# ComponentTester.net
KiCad netlist of a schematic drawn in EAGLE
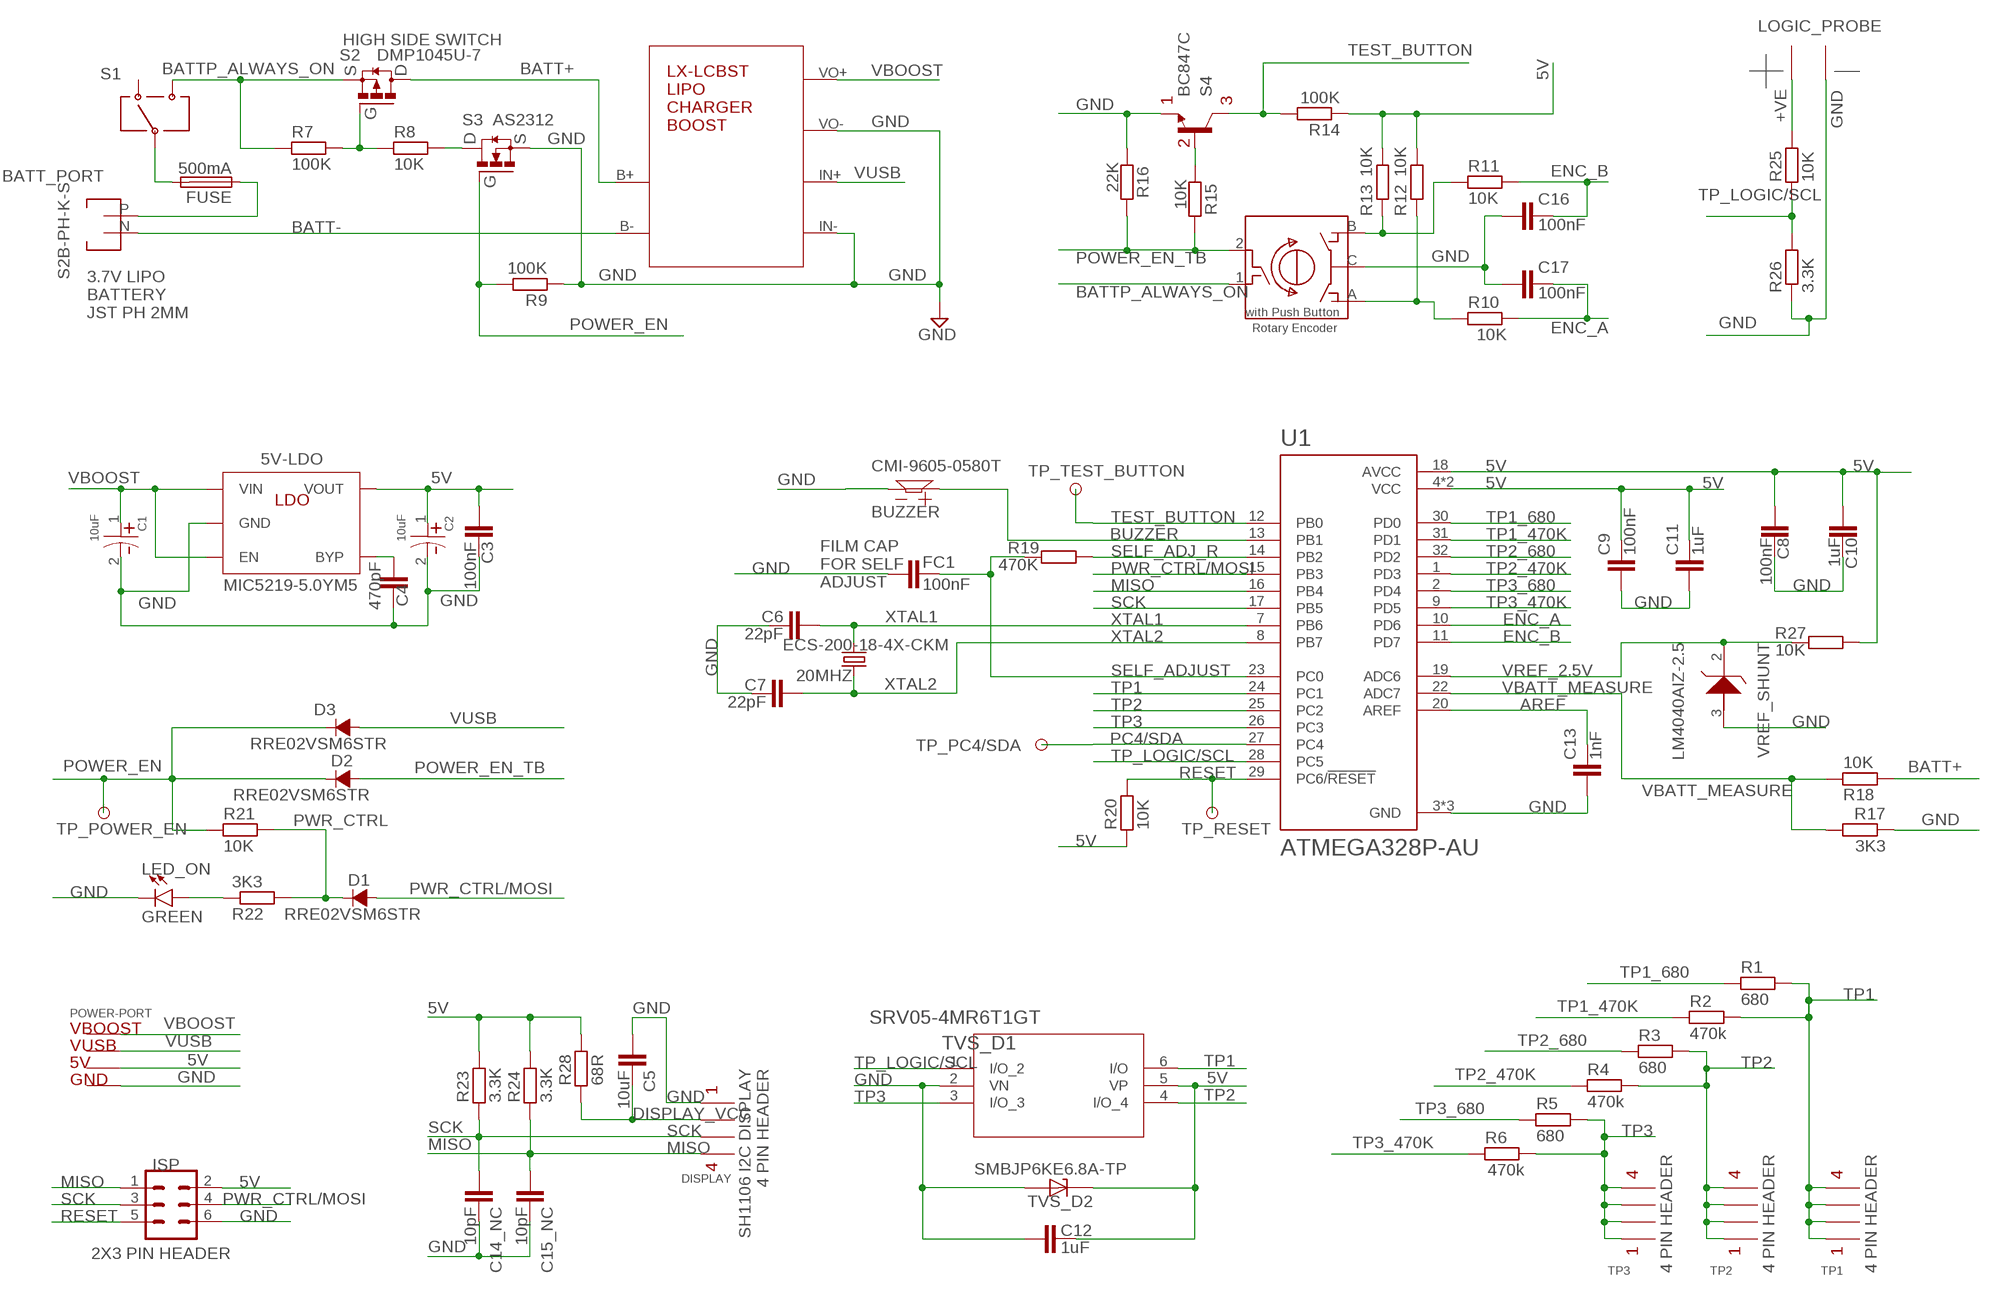
[diagram p0: schematic, sheet 1]

(export (version "E")
  (design (tool "Eeschema 10.0.6"))
  (components
    (comp (ref "5V-LDO")
      (value "MIC5219-5.0YM5")
      (footprint "eagle-import:SOT-23-5")
      (libsource (lib "eagle-import") (part "MIC5219-5.0YM5"))
    )
    (comp (ref "20MHZ")
      (value "ECS-200-18-4X-CKM")
      (footprint "eagle-import:XTAL_ECS-200-18-4X-CKM")
      (fields (field (name "DIGIKEY_PART_NUMBER") "50-ECS-200-18-4X-CKM-ND") (field (name "MF") "ECS Inc."))
      (libsource (lib "eagle-import") (part "ECS-200-18-4X-CKM"))
    )
    (comp (ref "BATT_PORT")
      (value "S2B-PH-K-S")
      (footprint "eagle-import:S2B-PH-K-S")
      (libsource (lib "eagle-import") (part "S2B-PH-K-S"))
    )
    (comp (ref "BUZZER")
      (value "CMI-9605-0580T")
      (footprint "eagle-import:BUZZER_CMI-9605-0580T")
      (libsource (lib "eagle-import") (part "BUZZER_CMI-9605-0580T"))
    )
    (comp (ref "C1")
      (value "10uF")
      (footprint "eagle-import:1206_DIRECTED")
      (libsource (lib "eagle-import") (part "CAPACITOR_TANTALUM_SMD1206"))
    )
    (comp (ref "C2")
      (value "10uF")
      (footprint "eagle-import:1206_DIRECTED")
      (libsource (lib "eagle-import") (part "CAPACITOR_TANTALUM_SMD1206"))
    )
    (comp (ref "C3")
      (value "100nF")
      (footprint "eagle-import:0603")
      (libsource (lib "eagle-import") (part "CAPACITOR_SMD0603"))
    )
    (comp (ref "C4")
      (value "470pF")
      (footprint "eagle-import:0603")
      (libsource (lib "eagle-import") (part "CAPACITOR_SMD0603"))
    )
    (comp (ref "C5")
      (value "10uF")
      (footprint "eagle-import:0603")
      (libsource (lib "eagle-import") (part "CAPACITOR_SMD0603"))
    )
    (comp (ref "C6")
      (value "22pF")
      (footprint "eagle-import:0603")
      (libsource (lib "eagle-import") (part "CAPACITOR_SMD0603"))
    )
    (comp (ref "C7")
      (value "22pF")
      (footprint "eagle-import:0603")
      (libsource (lib "eagle-import") (part "CAPACITOR_SMD0603"))
    )
    (comp (ref "C8")
      (value "100nF")
      (footprint "eagle-import:1206")
      (libsource (lib "eagle-import") (part "CAPACITOR_SMD1206"))
    )
    (comp (ref "C9")
      (value "100nF")
      (footprint "eagle-import:1206")
      (libsource (lib "eagle-import") (part "CAPACITOR_SMD1206"))
    )
    (comp (ref "C10")
      (value "1uF")
      (footprint "eagle-import:1206")
      (libsource (lib "eagle-import") (part "CAPACITOR_SMD1206"))
    )
    (comp (ref "C11")
      (value "1uF")
      (footprint "eagle-import:1206")
      (libsource (lib "eagle-import") (part "CAPACITOR_SMD1206"))
    )
    (comp (ref "C12")
      (value "1uF")
      (footprint "eagle-import:0603")
      (libsource (lib "eagle-import") (part "CAPACITOR_SMD0603"))
    )
    (comp (ref "C13")
      (value "1nF")
      (footprint "eagle-import:0603")
      (libsource (lib "eagle-import") (part "CAPACITOR_SMD0603"))
    )
    (comp (ref "C14_NC")
      (value "10pF")
      (footprint "eagle-import:0603")
      (libsource (lib "eagle-import") (part "CAPACITOR_SMD0603"))
    )
    (comp (ref "C15_NC")
      (value "10pF")
      (footprint "eagle-import:0603")
      (libsource (lib "eagle-import") (part "CAPACITOR_SMD0603"))
    )
    (comp (ref "C16")
      (value "100nF")
      (footprint "eagle-import:0603")
      (libsource (lib "eagle-import") (part "CAPACITOR_SMD0603"))
    )
    (comp (ref "C17")
      (value "100nF")
      (footprint "eagle-import:0603")
      (libsource (lib "eagle-import") (part "CAPACITOR_SMD0603"))
    )
    (comp (ref "CHARGE_BOOST")
      (value "LX-LCBST_LIPO_CHARGER_BOOST")
      (footprint "eagle-import:LX-LCBST_LIPO_CHARGER_BOOST")
      (libsource (lib "eagle-import") (part "LX-LCBST_LIPO_CHARGER_BOOST"))
    )
    (comp (ref "D1")
      (value "RRE02VSM6STR")
      (footprint "eagle-import:TUMD2SM-2")
      (libsource (lib "eagle-import") (part "RRE02VSM6S"))
    )
    (comp (ref "D2")
      (value "RRE02VSM6STR")
      (footprint "eagle-import:TUMD2SM-2")
      (libsource (lib "eagle-import") (part "RRE02VSM6S"))
    )
    (comp (ref "D3")
      (value "RRE02VSM6STR")
      (footprint "eagle-import:TUMD2SM-2")
      (libsource (lib "eagle-import") (part "RRE02VSM6S"))
    )
    (comp (ref "DISPLAY")
      (value "SH1106_I2C_DISPLAY")
      (footprint "eagle-import:SH1106_1.3IN_I2C_DISPLAY")
      (libsource (lib "eagle-import") (part "SH1106_I2C_DISPLAY"))
    )
    (comp (ref "ENC")
      (value "PEC12R-3217F-S0024-ND")
      (footprint "eagle-import:PEC12R-3217F-S0024")
      (libsource (lib "eagle-import") (part "PEC12R-3217F-S0024"))
    )
    (comp (ref "FC1")
      (value "100nF")
      (footprint "eagle-import:0805")
      (libsource (lib "eagle-import") (part "CAPACITOR_SMD0805"))
    )
    (comp (ref "FUSE")
      (value "500mA")
      (footprint "eagle-import:1206")
      (libsource (lib "eagle-import") (part "FUSE"))
    )
    (comp (ref "ISP")
      (value "2X3 PIN HEADER")
      (footprint "eagle-import:ISP_HEADER")
      (libsource (lib "eagle-import") (part "ISP_HEADER"))
    )
    (comp (ref "LED_ON")
      (value "GREEN")
      (footprint "eagle-import:1206_DIODE")
      (libsource (lib "eagle-import") (part "LED1206"))
    )
    (comp (ref "LOGIC_PROBE")
      (value "5MM_PIN_HEADER")
      (footprint "eagle-import:5MM_PIN_HEADER")
      (libsource (lib "eagle-import") (part "5MM_PIN_HEADER"))
    )
    (comp (ref "POWER-PORT")
      (value "POWER_OUT_4_PIN_HEADER")
      (footprint "eagle-import:POWER_OUT_4_PIN_HEADER")
      (libsource (lib "eagle-import") (part "POWER_OUT_4_PIN_HEADER"))
    )
    (comp (ref "R1")
      (value "680")
      (footprint "eagle-import:1206")
      (libsource (lib "eagle-import") (part "RESISTOR_SMD1206"))
    )
    (comp (ref "R2")
      (value "470k")
      (footprint "eagle-import:1206")
      (libsource (lib "eagle-import") (part "RESISTOR_SMD1206"))
    )
    (comp (ref "R3")
      (value "680")
      (footprint "eagle-import:1206")
      (libsource (lib "eagle-import") (part "RESISTOR_SMD1206"))
    )
    (comp (ref "R4")
      (value "470k")
      (footprint "eagle-import:1206")
      (libsource (lib "eagle-import") (part "RESISTOR_SMD1206"))
    )
    (comp (ref "R5")
      (value "680")
      (footprint "eagle-import:1206")
      (libsource (lib "eagle-import") (part "RESISTOR_SMD1206"))
    )
    (comp (ref "R6")
      (value "470k")
      (footprint "eagle-import:1206")
      (libsource (lib "eagle-import") (part "RESISTOR_SMD1206"))
    )
    (comp (ref "R7")
      (value "100K")
      (footprint "eagle-import:0603")
      (libsource (lib "eagle-import") (part "RESISTOR_SMD0603"))
    )
    (comp (ref "R8")
      (value "10K")
      (footprint "eagle-import:0603")
      (libsource (lib "eagle-import") (part "RESISTOR_SMD0603"))
    )
    (comp (ref "R9")
      (value "100K")
      (footprint "eagle-import:0603")
      (libsource (lib "eagle-import") (part "RESISTOR_SMD0603"))
    )
    (comp (ref "R10")
      (value "10K")
      (footprint "eagle-import:0603")
      (libsource (lib "eagle-import") (part "RESISTOR_SMD0603"))
    )
    (comp (ref "R11")
      (value "10K")
      (footprint "eagle-import:0603")
      (libsource (lib "eagle-import") (part "RESISTOR_SMD0603"))
    )
    (comp (ref "R12")
      (value "10K")
      (footprint "eagle-import:0603")
      (libsource (lib "eagle-import") (part "RESISTOR_SMD0603"))
    )
    (comp (ref "R13")
      (value "10K")
      (footprint "eagle-import:0603")
      (libsource (lib "eagle-import") (part "RESISTOR_SMD0603"))
    )
    (comp (ref "R14")
      (value "100K")
      (footprint "eagle-import:0603")
      (libsource (lib "eagle-import") (part "RESISTOR_SMD0603"))
    )
    (comp (ref "R15")
      (value "10K")
      (footprint "eagle-import:0603")
      (libsource (lib "eagle-import") (part "RESISTOR_SMD0603"))
    )
    (comp (ref "R16")
      (value "22K")
      (footprint "eagle-import:0603")
      (libsource (lib "eagle-import") (part "RESISTOR_SMD0603"))
    )
    (comp (ref "R17")
      (value "3K3")
      (footprint "eagle-import:0603")
      (libsource (lib "eagle-import") (part "RESISTOR_SMD0603"))
    )
    (comp (ref "R18")
      (value "10K")
      (footprint "eagle-import:0603")
      (libsource (lib "eagle-import") (part "RESISTOR_SMD0603"))
    )
    (comp (ref "R19")
      (value "470K")
      (footprint "eagle-import:0603")
      (libsource (lib "eagle-import") (part "RESISTOR_SMD0603"))
    )
    (comp (ref "R20")
      (value "10K")
      (footprint "eagle-import:0603")
      (libsource (lib "eagle-import") (part "RESISTOR_SMD0603"))
    )
    (comp (ref "R21")
      (value "10K")
      (footprint "eagle-import:0603")
      (libsource (lib "eagle-import") (part "RESISTOR_SMD0603"))
    )
    (comp (ref "R22")
      (value "3K3")
      (footprint "eagle-import:0603")
      (libsource (lib "eagle-import") (part "RESISTOR_SMD0603"))
    )
    (comp (ref "R23")
      (value "3.3K")
      (footprint "eagle-import:0603")
      (libsource (lib "eagle-import") (part "RESISTOR_SMD0603"))
    )
    (comp (ref "R24")
      (value "3.3K")
      (footprint "eagle-import:0603")
      (libsource (lib "eagle-import") (part "RESISTOR_SMD0603"))
    )
    (comp (ref "R25")
      (value "10K")
      (footprint "eagle-import:1206")
      (libsource (lib "eagle-import") (part "RESISTOR_SMD1206"))
    )
    (comp (ref "R26")
      (value "3.3K")
      (footprint "eagle-import:1206")
      (libsource (lib "eagle-import") (part "RESISTOR_SMD1206"))
    )
    (comp (ref "R27")
      (value "10K")
      (footprint "eagle-import:0603")
      (libsource (lib "eagle-import") (part "RESISTOR_SMD0603"))
    )
    (comp (ref "R28")
      (value "68R")
      (footprint "eagle-import:0603")
      (libsource (lib "eagle-import") (part "RESISTOR_SMD0603"))
    )
    (comp (ref "S1")
      (value "SLW-913535-2A-RA-D")
      (footprint "eagle-import:SLW-913535-2A-RA-D")
      (libsource (lib "eagle-import") (part "SLW-913535-2A-RA-D"))
    )
    (comp (ref "S2")
      (value "DMP1045U-7")
      (footprint "eagle-import:SOT-23-3")
      (libsource (lib "eagle-import") (part "PMOSFET"))
    )
    (comp (ref "S3")
      (value "AS2312")
      (footprint "eagle-import:SOT-23-3")
      (libsource (lib "eagle-import") (part "G6N02L"))
    )
    (comp (ref "S4")
      (value "BC847C")
      (footprint "eagle-import:SOT-23-3")
      (libsource (lib "eagle-import") (part "BC847C"))
    )
    (comp (ref "TP1")
      (value "4_PIN_HEADER")
      (footprint "eagle-import:4_PIN_HEADER")
      (libsource (lib "eagle-import") (part "4_PIN_HEADER"))
    )
    (comp (ref "TP2")
      (value "4_PIN_HEADER")
      (footprint "eagle-import:4_PIN_HEADER")
      (libsource (lib "eagle-import") (part "4_PIN_HEADER"))
    )
    (comp (ref "TP3")
      (value "4_PIN_HEADER")
      (footprint "eagle-import:4_PIN_HEADER")
      (libsource (lib "eagle-import") (part "4_PIN_HEADER"))
    )
    (comp (ref "TP_PC4/SDA")
      (value "TEST_POINT")
      (footprint "eagle-import:TEST_POINT")
      (libsource (lib "eagle-import") (part "TEST_POINT"))
    )
    (comp (ref "TP_POWER_EN")
      (value "TEST_POINT")
      (footprint "eagle-import:TEST_POINT")
      (libsource (lib "eagle-import") (part "TEST_POINT"))
    )
    (comp (ref "TP_RESET")
      (value "TEST_POINT")
      (footprint "eagle-import:TEST_POINT")
      (libsource (lib "eagle-import") (part "TEST_POINT"))
    )
    (comp (ref "TP_TEST_BUTTON")
      (value "TEST_POINT")
      (footprint "eagle-import:TEST_POINT")
      (libsource (lib "eagle-import") (part "TEST_POINT"))
    )
    (comp (ref "TVS_D1")
      (value "SRV05-4MR6T1GT")
      (footprint "eagle-import:TSOP6_3P1X1P7_ONS")
      (fields
        (field (name "MANUFACTURER_PART_NUMBER") "SRV05-4MR6T1G")
        (field (name "COPYRIGHT") "Copyright (C) 2023 Ultra Librarian. All rights reserved.")
      )
      (libsource (lib "eagle-import") (part "SRV05-4MR6T1GTSOP6_3P1X1P7_ONS"))
    )
    (comp (ref "TVS_D2")
      (value "SMBJP6KE6.8A-TP")
      (footprint "eagle-import:DIOM5336X244N")
      (fields
        (field (name "DIGIKEY_PART_NUMBER") "SMBJP6KE6.8A-TPMSTR-ND")
        (field (name "MF") "Micro Commercial")
      )
      (libsource (lib "eagle-import") (part "SMBJP6KE6.8A-TP"))
    )
    (comp (ref "U1")
      (value "ATMEGA328P-AU")
      (footprint "eagle-import:QFP80P900X900X120-32N")
      (fields (field (name "MF") "Microchip"))
      (libsource (lib "eagle-import") (part "ATMEGA328P-AU"))
    )
    (comp (ref "VREF_SHUNT")
      (value "LM4040AIZ-2.5")
      (footprint "eagle-import:TO92-3")
      (libsource (lib "eagle-import") (part "LM4040AIZ-2.5/NOPB"))
    )
  )
  (nets
    (net (code "1") (name "/+VE") (class "Default")
      (node (ref "LOGIC_PROBE") (pin "P$1") (pinfunction "P$1_P$1") (pintype "bidirectional"))
      (node (ref "R25") (pin "2") (pinfunction "2_2") (pintype "passive"))
    )
    (net (code "2") (name "/5V") (class "Default")
      (node (ref "5V-LDO") (pin "5") (pinfunction "VOUT_5") (pintype "bidirectional"))
      (node (ref "C10") (pin "2") (pinfunction "2_2") (pintype "passive"))
      (node (ref "C11") (pin "1") (pinfunction "1_1") (pintype "passive"))
      (node (ref "C12") (pin "1") (pinfunction "1_1") (pintype "passive"))
      (node (ref "C2") (pin "1") (pinfunction "P_1") (pintype "bidirectional"))
      (node (ref "C3") (pin "2") (pinfunction "2_2") (pintype "passive"))
      (node (ref "C8") (pin "2") (pinfunction "2_2") (pintype "passive"))
      (node (ref "C9") (pin "1") (pinfunction "1_1") (pintype "passive"))
      (node (ref "ISP") (pin "2") (pinfunction "2_2") (pintype "passive"))
      (node (ref "POWER-PORT") (pin "5V") (pinfunction "5V_5V") (pintype "bidirectional"))
      (node (ref "R12") (pin "2") (pinfunction "2_2") (pintype "passive"))
      (node (ref "R13") (pin "2") (pinfunction "2_2") (pintype "passive"))
      (node (ref "R14") (pin "1") (pinfunction "1_1") (pintype "passive"))
      (node (ref "R20") (pin "1") (pinfunction "1_1") (pintype "passive"))
      (node (ref "R23") (pin "2") (pinfunction "2_2") (pintype "passive"))
      (node (ref "R24") (pin "2") (pinfunction "2_2") (pintype "passive"))
      (node (ref "R27") (pin "1") (pinfunction "1_1") (pintype "passive"))
      (node (ref "R28") (pin "2") (pinfunction "2_2") (pintype "passive"))
      (node (ref "TVS_D1") (pin "5") (pinfunction "VP_5") (pintype "power_in"))
      (node (ref "TVS_D2") (pin "C") (pinfunction "C_C") (pintype "passive"))
      (node (ref "U1") (pin "18") (pinfunction "AVCC_18") (pintype "power_in"))
      (node (ref "U1") (pin "4") (pinfunction "VCC_4") (pintype "power_in"))
      (node (ref "U1") (pin "6") (pinfunction "VCC_6") (pintype "power_in"))
    )
    (net (code "3") (name "/AREF") (class "Default")
      (node (ref "C13") (pin "1") (pinfunction "1_1") (pintype "passive"))
      (node (ref "U1") (pin "20") (pinfunction "AREF_20") (pintype "input"))
    )
    (net (code "4") (name "/BATT+") (class "Default")
      (node (ref "CHARGE_BOOST") (pin "B+") (pinfunction "B+_B+") (pintype "bidirectional"))
      (node (ref "R18") (pin "2") (pinfunction "2_2") (pintype "passive"))
      (node (ref "S2") (pin "3") (pinfunction "D_3") (pintype "passive"))
    )
    (net (code "5") (name "/BATT-") (class "Default")
      (node (ref "BATT_PORT") (pin "N") (pinfunction "N_N") (pintype "bidirectional"))
      (node (ref "CHARGE_BOOST") (pin "B-") (pinfunction "B-_B-") (pintype "bidirectional"))
    )
    (net (code "6") (name "/BATTP_ALWAYS_ON") (class "Default")
      (node (ref "ENC") (pin "1") (pinfunction "1_1") (pintype "bidirectional"))
      (node (ref "R7") (pin "1") (pinfunction "1_1") (pintype "passive"))
      (node (ref "S1") (pin "3") (pinfunction "3_3") (pintype "bidirectional"))
      (node (ref "S2") (pin "2") (pinfunction "S_2") (pintype "passive"))
    )
    (net (code "7") (name "/BUZZER") (class "Default")
      (node (ref "BUZZER") (pin "P$1") (pinfunction "P$1_P$1") (pintype "bidirectional"))
      (node (ref "U1") (pin "13") (pinfunction "PB1_13") (pintype "bidirectional"))
    )
    (net (code "8") (name "/DISPLAY_VCC") (class "Default")
      (node (ref "C5") (pin "1") (pinfunction "1_1") (pintype "passive"))
      (node (ref "DISPLAY") (pin "VCC") (pinfunction "VCC_VCC") (pintype "bidirectional"))
      (node (ref "R28") (pin "1") (pinfunction "1_1") (pintype "passive"))
    )
    (net (code "9") (name "/ENC_A") (class "Default")
      (node (ref "C17") (pin "1") (pinfunction "1_1") (pintype "passive"))
      (node (ref "R10") (pin "2") (pinfunction "2_2") (pintype "passive"))
      (node (ref "U1") (pin "10") (pinfunction "PD6_10") (pintype "bidirectional"))
    )
    (net (code "10") (name "/ENC_B") (class "Default")
      (node (ref "C16") (pin "1") (pinfunction "1_1") (pintype "passive"))
      (node (ref "R11") (pin "2") (pinfunction "2_2") (pintype "passive"))
      (node (ref "U1") (pin "11") (pinfunction "PD7_11") (pintype "bidirectional"))
    )
    (net (code "11") (name "/MISO") (class "Default")
      (node (ref "C15_NC") (pin "2") (pinfunction "2_2") (pintype "passive"))
      (node (ref "DISPLAY") (pin "SDA") (pinfunction "SDA_SDA") (pintype "bidirectional"))
      (node (ref "ISP") (pin "1") (pinfunction "1_1") (pintype "passive"))
      (node (ref "R24") (pin "1") (pinfunction "1_1") (pintype "passive"))
      (node (ref "U1") (pin "16") (pinfunction "PB4_16") (pintype "bidirectional"))
    )
    (net (code "12") (name "/PC4{slash}SDA") (class "Default")
      (node (ref "TP_PC4/SDA") (pin "P$1") (pinfunction "P$1_P$1") (pintype "bidirectional"))
      (node (ref "U1") (pin "27") (pinfunction "PC4_27") (pintype "bidirectional"))
    )
    (net (code "13") (name "/POWER_EN") (class "Default")
      (node (ref "D2") (pin "C") (pinfunction "C_C") (pintype "bidirectional"))
      (node (ref "D3") (pin "C") (pinfunction "C_C") (pintype "bidirectional"))
      (node (ref "R21") (pin "1") (pinfunction "1_1") (pintype "passive"))
      (node (ref "R9") (pin "2") (pinfunction "2_2") (pintype "passive"))
      (node (ref "S3") (pin "1") (pinfunction "G_1") (pintype "passive"))
      (node (ref "TP_POWER_EN") (pin "P$1") (pinfunction "P$1_P$1") (pintype "bidirectional"))
    )
    (net (code "14") (name "/POWER_EN_TB") (class "Default")
      (node (ref "D2") (pin "A") (pinfunction "A_A") (pintype "bidirectional"))
      (node (ref "ENC") (pin "2") (pinfunction "2_2") (pintype "bidirectional"))
      (node (ref "R15") (pin "2") (pinfunction "2_2") (pintype "passive"))
      (node (ref "R16") (pin "2") (pinfunction "2_2") (pintype "passive"))
    )
    (net (code "15") (name "/PWR_CTRL") (class "Default")
      (node (ref "D1") (pin "C") (pinfunction "C_C") (pintype "bidirectional"))
      (node (ref "R21") (pin "2") (pinfunction "2_2") (pintype "passive"))
      (node (ref "R22") (pin "2") (pinfunction "2_2") (pintype "passive"))
    )
    (net (code "16") (name "/PWR_CTRL{slash}MOSI") (class "Default")
      (node (ref "D1") (pin "A") (pinfunction "A_A") (pintype "bidirectional"))
      (node (ref "ISP") (pin "4") (pinfunction "4_4") (pintype "passive"))
      (node (ref "U1") (pin "15") (pinfunction "PB3_15") (pintype "bidirectional"))
    )
    (net (code "17") (name "/RESET") (class "Default")
      (node (ref "ISP") (pin "5") (pinfunction "5_5") (pintype "passive"))
      (node (ref "R20") (pin "2") (pinfunction "2_2") (pintype "passive"))
      (node (ref "TP_RESET") (pin "P$1") (pinfunction "P$1_P$1") (pintype "bidirectional"))
      (node (ref "U1") (pin "29") (pinfunction "PC6/~{RESET}_29") (pintype "bidirectional"))
    )
    (net (code "18") (name "/SCK") (class "Default")
      (node (ref "C14_NC") (pin "2") (pinfunction "2_2") (pintype "passive"))
      (node (ref "DISPLAY") (pin "SCK") (pinfunction "SCK_SCK") (pintype "bidirectional"))
      (node (ref "ISP") (pin "3") (pinfunction "3_3") (pintype "passive"))
      (node (ref "R23") (pin "1") (pinfunction "1_1") (pintype "passive"))
      (node (ref "U1") (pin "17") (pinfunction "PB5_17") (pintype "bidirectional"))
    )
    (net (code "19") (name "/SELF_ADJUST") (class "Default")
      (node (ref "FC1") (pin "2") (pinfunction "2_2") (pintype "passive"))
      (node (ref "R19") (pin "2") (pinfunction "2_2") (pintype "passive"))
      (node (ref "U1") (pin "23") (pinfunction "PC0_23") (pintype "bidirectional"))
    )
    (net (code "20") (name "/SELF_ADJ_R") (class "Default")
      (node (ref "R19") (pin "1") (pinfunction "1_1") (pintype "passive"))
      (node (ref "U1") (pin "14") (pinfunction "PB2_14") (pintype "bidirectional"))
    )
    (net (code "21") (name "/TEST_BUTTON") (class "Default")
      (node (ref "R14") (pin "2") (pinfunction "2_2") (pintype "passive"))
      (node (ref "S4") (pin "3") (pinfunction "C_3") (pintype "passive"))
      (node (ref "TP_TEST_BUTTON") (pin "P$1") (pinfunction "P$1_P$1") (pintype "bidirectional"))
      (node (ref "U1") (pin "12") (pinfunction "PB0_12") (pintype "bidirectional"))
    )
    (net (code "22") (name "/TP1") (class "Default")
      (node (ref "R1") (pin "2") (pinfunction "2_2") (pintype "passive"))
      (node (ref "R2") (pin "2") (pinfunction "2_2") (pintype "passive"))
      (node (ref "TP1") (pin "P$1") (pinfunction "P$1_P$1") (pintype "bidirectional"))
      (node (ref "TP1") (pin "P$2") (pinfunction "P$2_P$2") (pintype "bidirectional"))
      (node (ref "TP1") (pin "P$3") (pinfunction "P$3_P$3") (pintype "bidirectional"))
      (node (ref "TP1") (pin "P$4") (pinfunction "P$4_P$4") (pintype "bidirectional"))
      (node (ref "TVS_D1") (pin "6") (pinfunction "I/O_6") (pintype "bidirectional"))
      (node (ref "U1") (pin "24") (pinfunction "PC1_24") (pintype "bidirectional"))
    )
    (net (code "23") (name "/TP1_470K") (class "Default")
      (node (ref "R2") (pin "1") (pinfunction "1_1") (pintype "passive"))
      (node (ref "U1") (pin "31") (pinfunction "PD1_31") (pintype "bidirectional"))
    )
    (net (code "24") (name "/TP1_680") (class "Default")
      (node (ref "R1") (pin "1") (pinfunction "1_1") (pintype "passive"))
      (node (ref "U1") (pin "30") (pinfunction "PD0_30") (pintype "bidirectional"))
    )
    (net (code "25") (name "/TP2") (class "Default")
      (node (ref "R3") (pin "2") (pinfunction "2_2") (pintype "passive"))
      (node (ref "R4") (pin "2") (pinfunction "2_2") (pintype "passive"))
      (node (ref "TP2") (pin "P$1") (pinfunction "P$1_P$1") (pintype "bidirectional"))
      (node (ref "TP2") (pin "P$2") (pinfunction "P$2_P$2") (pintype "bidirectional"))
      (node (ref "TP2") (pin "P$3") (pinfunction "P$3_P$3") (pintype "bidirectional"))
      (node (ref "TP2") (pin "P$4") (pinfunction "P$4_P$4") (pintype "bidirectional"))
      (node (ref "TVS_D1") (pin "4") (pinfunction "I/O_4_4") (pintype "bidirectional"))
      (node (ref "U1") (pin "25") (pinfunction "PC2_25") (pintype "bidirectional"))
    )
    (net (code "26") (name "/TP2_470K") (class "Default")
      (node (ref "R4") (pin "1") (pinfunction "1_1") (pintype "passive"))
      (node (ref "U1") (pin "1") (pinfunction "PD3_1") (pintype "bidirectional"))
    )
    (net (code "27") (name "/TP2_680") (class "Default")
      (node (ref "R3") (pin "1") (pinfunction "1_1") (pintype "passive"))
      (node (ref "U1") (pin "32") (pinfunction "PD2_32") (pintype "bidirectional"))
    )
    (net (code "28") (name "/TP3") (class "Default")
      (node (ref "R5") (pin "2") (pinfunction "2_2") (pintype "passive"))
      (node (ref "R6") (pin "2") (pinfunction "2_2") (pintype "passive"))
      (node (ref "TP3") (pin "P$1") (pinfunction "P$1_P$1") (pintype "bidirectional"))
      (node (ref "TP3") (pin "P$2") (pinfunction "P$2_P$2") (pintype "bidirectional"))
      (node (ref "TP3") (pin "P$3") (pinfunction "P$3_P$3") (pintype "bidirectional"))
      (node (ref "TP3") (pin "P$4") (pinfunction "P$4_P$4") (pintype "bidirectional"))
      (node (ref "TVS_D1") (pin "3") (pinfunction "I/O_3_3") (pintype "bidirectional"))
      (node (ref "U1") (pin "26") (pinfunction "PC3_26") (pintype "bidirectional"))
    )
    (net (code "29") (name "/TP3_470K") (class "Default")
      (node (ref "R6") (pin "1") (pinfunction "1_1") (pintype "passive"))
      (node (ref "U1") (pin "9") (pinfunction "PD5_9") (pintype "bidirectional"))
    )
    (net (code "30") (name "/TP3_680") (class "Default")
      (node (ref "R5") (pin "1") (pinfunction "1_1") (pintype "passive"))
      (node (ref "U1") (pin "2") (pinfunction "PD4_2") (pintype "bidirectional"))
    )
    (net (code "31") (name "/TP_LOGIC{slash}SCL") (class "Default")
      (node (ref "R25") (pin "1") (pinfunction "1_1") (pintype "passive"))
      (node (ref "R26") (pin "2") (pinfunction "2_2") (pintype "passive"))
      (node (ref "TVS_D1") (pin "1") (pinfunction "I/O_2_1") (pintype "bidirectional"))
      (node (ref "U1") (pin "28") (pinfunction "PC5_28") (pintype "bidirectional"))
    )
    (net (code "32") (name "/VBATT_MEASURE") (class "Default")
      (node (ref "R17") (pin "2") (pinfunction "2_2") (pintype "passive"))
      (node (ref "R18") (pin "1") (pinfunction "1_1") (pintype "passive"))
      (node (ref "U1") (pin "22") (pinfunction "ADC7_22") (pintype "bidirectional"))
    )
    (net (code "33") (name "/VBOOST") (class "Default")
      (node (ref "5V-LDO") (pin "1") (pinfunction "VIN_1") (pintype "bidirectional"))
      (node (ref "5V-LDO") (pin "3") (pinfunction "EN_3") (pintype "bidirectional"))
      (node (ref "C1") (pin "1") (pinfunction "P_1") (pintype "bidirectional"))
      (node (ref "CHARGE_BOOST") (pin "VO+") (pinfunction "VO+_VO+") (pintype "bidirectional"))
      (node (ref "POWER-PORT") (pin "VBOOST") (pinfunction "VBOOST_VBOOST") (pintype "bidirectional"))
    )
    (net (code "34") (name "/VREF_2.5V") (class "Default")
      (node (ref "R27") (pin "2") (pinfunction "2_2") (pintype "passive"))
      (node (ref "U1") (pin "19") (pinfunction "ADC6_19") (pintype "bidirectional"))
      (node (ref "VREF_SHUNT") (pin "2") (pinfunction "C_2") (pintype "bidirectional"))
    )
    (net (code "35") (name "/VUSB") (class "Default")
      (node (ref "CHARGE_BOOST") (pin "IN+") (pinfunction "USB+_IN+") (pintype "bidirectional"))
      (node (ref "D3") (pin "A") (pinfunction "A_A") (pintype "bidirectional"))
      (node (ref "POWER-PORT") (pin "VUSB") (pinfunction "VUSB_VUSB") (pintype "bidirectional"))
    )
    (net (code "36") (name "/XTAL1") (class "Default")
      (node (ref "20MHZ") (pin "2") (pinfunction "2_2") (pintype "passive"))
      (node (ref "C6") (pin "2") (pinfunction "2_2") (pintype "passive"))
      (node (ref "U1") (pin "7") (pinfunction "PB6_7") (pintype "bidirectional"))
    )
    (net (code "37") (name "/XTAL2") (class "Default")
      (node (ref "20MHZ") (pin "1") (pinfunction "1_1") (pintype "passive"))
      (node (ref "C7") (pin "2") (pinfunction "2_2") (pintype "passive"))
      (node (ref "U1") (pin "8") (pinfunction "PB7_8") (pintype "bidirectional"))
    )
    (net (code "38") (name "GND") (class "Default")
      (node (ref "5V-LDO") (pin "2") (pinfunction "GND_2") (pintype "bidirectional"))
      (node (ref "BUZZER") (pin "P$2") (pinfunction "P$2_P$2") (pintype "bidirectional"))
      (node (ref "C1") (pin "2") (pinfunction "N_2") (pintype "bidirectional"))
      (node (ref "C10") (pin "1") (pinfunction "1_1") (pintype "passive"))
      (node (ref "C11") (pin "2") (pinfunction "2_2") (pintype "passive"))
      (node (ref "C12") (pin "2") (pinfunction "2_2") (pintype "passive"))
      (node (ref "C13") (pin "2") (pinfunction "2_2") (pintype "passive"))
      (node (ref "C14_NC") (pin "1") (pinfunction "1_1") (pintype "passive"))
      (node (ref "C15_NC") (pin "1") (pinfunction "1_1") (pintype "passive"))
      (node (ref "C16") (pin "2") (pinfunction "2_2") (pintype "passive"))
      (node (ref "C17") (pin "2") (pinfunction "2_2") (pintype "passive"))
      (node (ref "C2") (pin "2") (pinfunction "N_2") (pintype "bidirectional"))
      (node (ref "C3") (pin "1") (pinfunction "1_1") (pintype "passive"))
      (node (ref "C4") (pin "1") (pinfunction "1_1") (pintype "passive"))
      (node (ref "C5") (pin "2") (pinfunction "2_2") (pintype "passive"))
      (node (ref "C6") (pin "1") (pinfunction "1_1") (pintype "passive"))
      (node (ref "C7") (pin "1") (pinfunction "1_1") (pintype "passive"))
      (node (ref "C8") (pin "1") (pinfunction "1_1") (pintype "passive"))
      (node (ref "C9") (pin "2") (pinfunction "2_2") (pintype "passive"))
      (node (ref "CHARGE_BOOST") (pin "IN-") (pinfunction "USB-_IN-") (pintype "bidirectional"))
      (node (ref "CHARGE_BOOST") (pin "VO-") (pinfunction "VO-_VO-") (pintype "bidirectional"))
      (node (ref "DISPLAY") (pin "GND") (pinfunction "GND_GND") (pintype "bidirectional"))
      (node (ref "ENC") (pin "C") (pinfunction "C_C") (pintype "bidirectional"))
      (node (ref "FC1") (pin "1") (pinfunction "1_1") (pintype "passive"))
      (node (ref "ISP") (pin "6") (pinfunction "6_6") (pintype "passive"))
      (node (ref "LED_ON") (pin "C") (pinfunction "C_C") (pintype "passive"))
      (node (ref "LOGIC_PROBE") (pin "P$2") (pinfunction "P$2_P$2") (pintype "bidirectional"))
      (node (ref "POWER-PORT") (pin "GND") (pinfunction "GND_GND") (pintype "bidirectional"))
      (node (ref "R16") (pin "1") (pinfunction "1_1") (pintype "passive"))
      (node (ref "R17") (pin "1") (pinfunction "1_1") (pintype "passive"))
      (node (ref "R26") (pin "1") (pinfunction "1_1") (pintype "passive"))
      (node (ref "R9") (pin "1") (pinfunction "1_1") (pintype "passive"))
      (node (ref "S3") (pin "2") (pinfunction "S_2") (pintype "passive"))
      (node (ref "S4") (pin "2") (pinfunction "E_2") (pintype "passive"))
      (node (ref "TVS_D1") (pin "2") (pinfunction "VN_2") (pintype "power_in"))
      (node (ref "TVS_D2") (pin "A") (pinfunction "A_A") (pintype "passive"))
      (node (ref "U1") (pin "21") (pinfunction "GND_21") (pintype "power_in"))
      (node (ref "U1") (pin "3") (pinfunction "GND_3") (pintype "power_in"))
      (node (ref "U1") (pin "5") (pinfunction "GND_5") (pintype "power_in"))
      (node (ref "VREF_SHUNT") (pin "3") (pinfunction "A_3") (pintype "bidirectional"))
    )
    (net (code "39") (name "Net-(5V-LDO-BYP)") (class "Default")
      (node (ref "5V-LDO") (pin "4") (pinfunction "BYP_4") (pintype "bidirectional"))
      (node (ref "C4") (pin "2") (pinfunction "2_2") (pintype "passive"))
    )
    (net (code "40") (name "Net-(BATT_PORT-PadP)") (class "Default")
      (node (ref "BATT_PORT") (pin "P") (pinfunction "P_P") (pintype "bidirectional"))
      (node (ref "FUSE") (pin "1") (pinfunction "1_1") (pintype "passive"))
    )
    (net (code "41") (name "Net-(ENC-PadA)") (class "Default")
      (node (ref "ENC") (pin "A") (pinfunction "A_A") (pintype "bidirectional"))
      (node (ref "R10") (pin "1") (pinfunction "1_1") (pintype "passive"))
      (node (ref "R12") (pin "1") (pinfunction "1_1") (pintype "passive"))
    )
    (net (code "42") (name "Net-(ENC-PadB)") (class "Default")
      (node (ref "ENC") (pin "B") (pinfunction "B_B") (pintype "bidirectional"))
      (node (ref "R11") (pin "1") (pinfunction "1_1") (pintype "passive"))
      (node (ref "R13") (pin "1") (pinfunction "1_1") (pintype "passive"))
    )
    (net (code "43") (name "Net-(FUSE-Pad2)") (class "Default")
      (node (ref "FUSE") (pin "2") (pinfunction "2_2") (pintype "passive"))
      (node (ref "S1") (pin "2") (pinfunction "2_2") (pintype "bidirectional"))
    )
    (net (code "44") (name "Net-(LED_ON-PadA)") (class "Default")
      (node (ref "LED_ON") (pin "A") (pinfunction "A_A") (pintype "passive"))
      (node (ref "R22") (pin "1") (pinfunction "1_1") (pintype "passive"))
    )
    (net (code "45") (name "Net-(S2-G)") (class "Default")
      (node (ref "R7") (pin "2") (pinfunction "2_2") (pintype "passive"))
      (node (ref "R8") (pin "1") (pinfunction "1_1") (pintype "passive"))
      (node (ref "S2") (pin "1") (pinfunction "G_1") (pintype "passive"))
    )
    (net (code "46") (name "Net-(S3-D)") (class "Default")
      (node (ref "R8") (pin "2") (pinfunction "2_2") (pintype "passive"))
      (node (ref "S3") (pin "3") (pinfunction "D_3") (pintype "passive"))
    )
    (net (code "47") (name "Net-(S4-B)") (class "Default")
      (node (ref "R15") (pin "1") (pinfunction "1_1") (pintype "passive"))
      (node (ref "S4") (pin "1") (pinfunction "B_1") (pintype "passive"))
    )
    (net (code "48") (name "unconnected-(S1-Pad1)") (class "Default")
      (node (ref "S1") (pin "1") (pinfunction "1_1") (pintype "bidirectional"))
    )
  )
)
